# Control_Acceso.net
KiCad netlist of a schematic drawn in Altium Designer
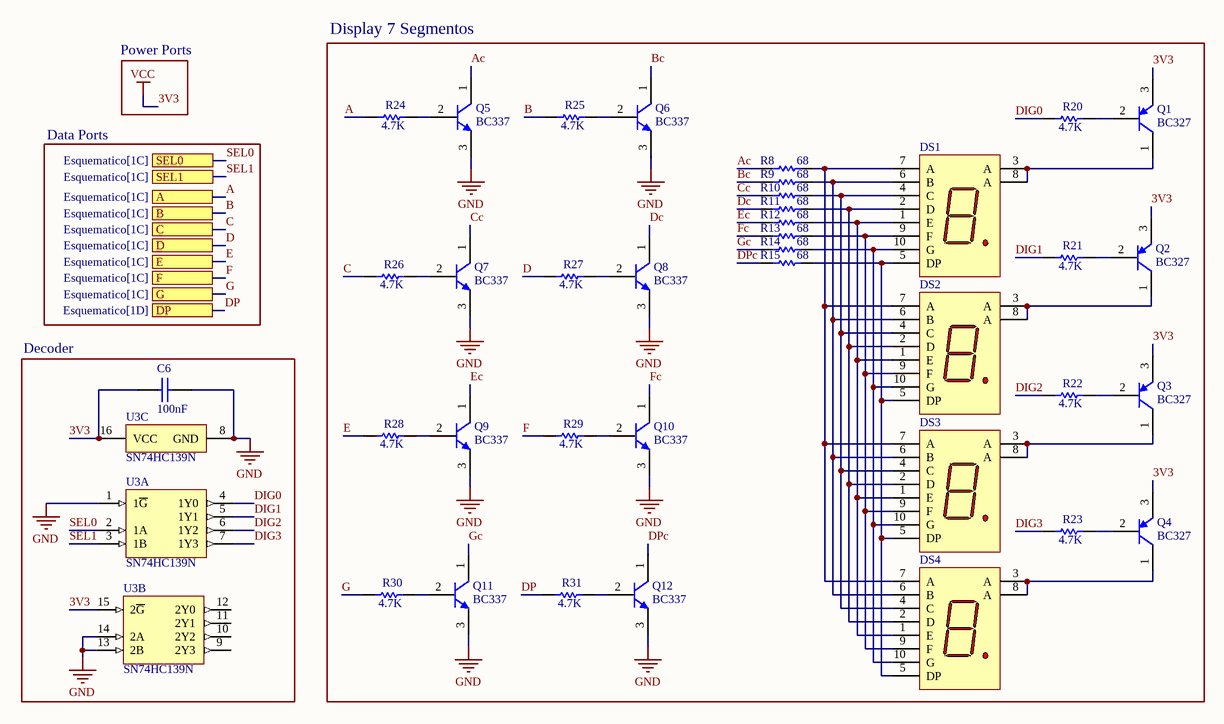
[diagram p0: Control_Acceso.SchDoc]

(export (version "E")
  (design (tool "Eeschema 10.0.6"))
  (components
    (comp (ref "C6")
      (value "100nF")
      (footprint "CAP200")
      (description "Multilayer Ceramic Capacitor")
      (libsource (lib "LIB PIO IX") (part "CAP"))
    )
    (comp (ref "DS1")
      (value "~")
      (footprint "WL-T7DS_L17.5W12.4H7")
      (description "7-Seg Display, Comm Anode, Super Red Rohs Compliant: Yes")
      (libsource (lib "Altium Content Vault") (part "7 Segments_Red_CA_type 1"))
    )
    (comp (ref "DS2")
      (value "~")
      (footprint "WL-T7DS_L17.5W12.4H7")
      (description "7-Seg Display, Comm Anode, Super Red Rohs Compliant: Yes")
      (libsource (lib "Altium Content Vault") (part "7 Segments_Red_CA_type 1"))
    )
    (comp (ref "DS3")
      (value "~")
      (footprint "WL-T7DS_L17.5W12.4H7")
      (description "7-Seg Display, Comm Anode, Super Red Rohs Compliant: Yes")
      (libsource (lib "Altium Content Vault") (part "7 Segments_Red_CA_type 1"))
    )
    (comp (ref "DS4")
      (value "~")
      (footprint "WL-T7DS_L17.5W12.4H7")
      (description "7-Seg Display, Comm Anode, Super Red Rohs Compliant: Yes")
      (libsource (lib "Altium Content Vault") (part "7 Segments_Red_CA_type 1"))
    )
    (comp (ref "Q1")
      (value "BC327")
      (footprint "ONSC-TO-92-3-29-11_AM_BL")
      (description "Amplifier Transistor, PNP Silicon, 3-Pin TO-92, Pb-Free, Ammo Box")
      (fields (field (name "MANUFACTURER") "On Semiconductor") (field (name "PARTNUMBER") "BC327-25ZL1G"))
      (libsource (lib "Altium Content Vault") (part "ONSC-PNP-C1B2E3-3"))
    )
    (comp (ref "Q2")
      (value "BC327")
      (footprint "ONSC-TO-92-3-29-11_AM_BL")
      (description "Amplifier Transistor, PNP Silicon, 3-Pin TO-92, Pb-Free, Ammo Box")
      (fields (field (name "MANUFACTURER") "On Semiconductor") (field (name "PARTNUMBER") "BC327-25ZL1G"))
      (libsource (lib "Altium Content Vault") (part "ONSC-PNP-C1B2E3-3"))
    )
    (comp (ref "Q3")
      (value "BC327")
      (footprint "ONSC-TO-92-3-29-11_AM_BL")
      (description "Amplifier Transistor, PNP Silicon, 3-Pin TO-92, Pb-Free, Ammo Box")
      (fields (field (name "MANUFACTURER") "On Semiconductor") (field (name "PARTNUMBER") "BC327-25ZL1G"))
      (libsource (lib "Altium Content Vault") (part "ONSC-PNP-C1B2E3-3"))
    )
    (comp (ref "Q4")
      (value "BC327")
      (footprint "ONSC-TO-92-3-29-11_AM_BL")
      (description "Amplifier Transistor, PNP Silicon, 3-Pin TO-92, Pb-Free, Ammo Box")
      (fields (field (name "MANUFACTURER") "On Semiconductor") (field (name "PARTNUMBER") "BC327-25ZL1G"))
      (libsource (lib "Altium Content Vault") (part "ONSC-PNP-C1B2E3-3"))
    )
    (comp (ref "Q5")
      (value "BC337")
      (footprint "ONSC-TO-92-3-29-11_AM_BL")
      (description "Amplifier Transistor, NPN Silicon, 3-Pin TO-92, Pb-Free, Ammo Box")
      (fields (field (name "PARTNUMBER") "BC337-40ZL1G") (field (name "MANUFACTURER") "On Semiconductor"))
      (libsource (lib "Altium Content Vault") (part "ONSC-NPN-C1B2E3-3"))
    )
    (comp (ref "Q6")
      (value "BC337")
      (footprint "ONSC-TO-92-3-29-11_AM_BL")
      (description "Amplifier Transistor, NPN Silicon, 3-Pin TO-92, Pb-Free, Ammo Box")
      (fields (field (name "PARTNUMBER") "BC337-40ZL1G") (field (name "MANUFACTURER") "On Semiconductor"))
      (libsource (lib "Altium Content Vault") (part "ONSC-NPN-C1B2E3-3"))
    )
    (comp (ref "Q7")
      (value "BC337")
      (footprint "ONSC-TO-92-3-29-11_AM_BL")
      (description "Amplifier Transistor, NPN Silicon, 3-Pin TO-92, Pb-Free, Ammo Box")
      (fields (field (name "PARTNUMBER") "BC337-40ZL1G") (field (name "MANUFACTURER") "On Semiconductor"))
      (libsource (lib "Altium Content Vault") (part "ONSC-NPN-C1B2E3-3"))
    )
    (comp (ref "Q8")
      (value "BC337")
      (footprint "ONSC-TO-92-3-29-11_AM_BL")
      (description "Amplifier Transistor, NPN Silicon, 3-Pin TO-92, Pb-Free, Ammo Box")
      (fields (field (name "PARTNUMBER") "BC337-40ZL1G") (field (name "MANUFACTURER") "On Semiconductor"))
      (libsource (lib "Altium Content Vault") (part "ONSC-NPN-C1B2E3-3"))
    )
    (comp (ref "Q9")
      (value "BC337")
      (footprint "ONSC-TO-92-3-29-11_AM_BL")
      (description "Amplifier Transistor, NPN Silicon, 3-Pin TO-92, Pb-Free, Ammo Box")
      (fields (field (name "PARTNUMBER") "BC337-40ZL1G") (field (name "MANUFACTURER") "On Semiconductor"))
      (libsource (lib "Altium Content Vault") (part "ONSC-NPN-C1B2E3-3"))
    )
    (comp (ref "Q10")
      (value "BC337")
      (footprint "ONSC-TO-92-3-29-11_AM_BL")
      (description "Amplifier Transistor, NPN Silicon, 3-Pin TO-92, Pb-Free, Ammo Box")
      (fields (field (name "PARTNUMBER") "BC337-40ZL1G") (field (name "MANUFACTURER") "On Semiconductor"))
      (libsource (lib "Altium Content Vault") (part "ONSC-NPN-C1B2E3-3"))
    )
    (comp (ref "Q11")
      (value "BC337")
      (footprint "ONSC-TO-92-3-29-11_AM_BL")
      (description "Amplifier Transistor, NPN Silicon, 3-Pin TO-92, Pb-Free, Ammo Box")
      (fields (field (name "PARTNUMBER") "BC337-40ZL1G") (field (name "MANUFACTURER") "On Semiconductor"))
      (libsource (lib "Altium Content Vault") (part "ONSC-NPN-C1B2E3-3"))
    )
    (comp (ref "Q12")
      (value "BC337")
      (footprint "ONSC-TO-92-3-29-11_AM_BL")
      (description "Amplifier Transistor, NPN Silicon, 3-Pin TO-92, Pb-Free, Ammo Box")
      (fields (field (name "PARTNUMBER") "BC337-40ZL1G") (field (name "MANUFACTURER") "On Semiconductor"))
      (libsource (lib "Altium Content Vault") (part "ONSC-NPN-C1B2E3-3"))
    )
    (comp (ref "R8")
      (value "68")
      (footprint "RES400")
      (description "Through Hole Resistor 1/8W Carbon Film")
      (libsource (lib "LIB PIO IX") (part "RES"))
    )
    (comp (ref "R9")
      (value "68")
      (footprint "RES400")
      (description "Through Hole Resistor 1/8W Carbon Film")
      (libsource (lib "LIB PIO IX") (part "RES"))
    )
    (comp (ref "R10")
      (value "68")
      (footprint "RES400")
      (description "Through Hole Resistor 1/8W Carbon Film")
      (libsource (lib "LIB PIO IX") (part "RES"))
    )
    (comp (ref "R11")
      (value "68")
      (footprint "RES400")
      (description "Through Hole Resistor 1/8W Carbon Film")
      (libsource (lib "LIB PIO IX") (part "RES"))
    )
    (comp (ref "R12")
      (value "68")
      (footprint "RES400")
      (description "Through Hole Resistor 1/8W Carbon Film")
      (libsource (lib "LIB PIO IX") (part "RES"))
    )
    (comp (ref "R13")
      (value "68")
      (footprint "RES400")
      (description "Through Hole Resistor 1/8W Carbon Film")
      (libsource (lib "LIB PIO IX") (part "RES"))
    )
    (comp (ref "R14")
      (value "68")
      (footprint "RES400")
      (description "Through Hole Resistor 1/8W Carbon Film")
      (libsource (lib "LIB PIO IX") (part "RES"))
    )
    (comp (ref "R15")
      (value "68")
      (footprint "RES400")
      (description "Through Hole Resistor 1/8W Carbon Film")
      (libsource (lib "LIB PIO IX") (part "RES"))
    )
    (comp (ref "R20")
      (value "4.7K")
      (footprint "RES400")
      (description "Through Hole Resistor 1/8W Carbon Film")
      (libsource (lib "LIB PIO IX") (part "RES"))
    )
    (comp (ref "R21")
      (value "4.7K")
      (footprint "RES400")
      (description "Through Hole Resistor 1/8W Carbon Film")
      (libsource (lib "LIB PIO IX") (part "RES"))
    )
    (comp (ref "R22")
      (value "4.7K")
      (footprint "RES400")
      (description "Through Hole Resistor 1/8W Carbon Film")
      (libsource (lib "LIB PIO IX") (part "RES"))
    )
    (comp (ref "R23")
      (value "4.7K")
      (footprint "RES400")
      (description "Through Hole Resistor 1/8W Carbon Film")
      (libsource (lib "LIB PIO IX") (part "RES"))
    )
    (comp (ref "R24")
      (value "4.7K")
      (footprint "RES400")
      (description "Through Hole Resistor 1/8W Carbon Film")
      (libsource (lib "LIB PIO IX") (part "RES"))
    )
    (comp (ref "R25")
      (value "4.7K")
      (footprint "RES400")
      (description "Through Hole Resistor 1/8W Carbon Film")
      (libsource (lib "LIB PIO IX") (part "RES"))
    )
    (comp (ref "R26")
      (value "4.7K")
      (footprint "RES400")
      (description "Through Hole Resistor 1/8W Carbon Film")
      (libsource (lib "LIB PIO IX") (part "RES"))
    )
    (comp (ref "R27")
      (value "4.7K")
      (footprint "RES400")
      (description "Through Hole Resistor 1/8W Carbon Film")
      (libsource (lib "LIB PIO IX") (part "RES"))
    )
    (comp (ref "R28")
      (value "4.7K")
      (footprint "RES400")
      (description "Through Hole Resistor 1/8W Carbon Film")
      (libsource (lib "LIB PIO IX") (part "RES"))
    )
    (comp (ref "R29")
      (value "4.7K")
      (footprint "RES400")
      (description "Through Hole Resistor 1/8W Carbon Film")
      (libsource (lib "LIB PIO IX") (part "RES"))
    )
    (comp (ref "R30")
      (value "4.7K")
      (footprint "RES400")
      (description "Through Hole Resistor 1/8W Carbon Film")
      (libsource (lib "LIB PIO IX") (part "RES"))
    )
    (comp (ref "R31")
      (value "4.7K")
      (footprint "RES400")
      (description "Through Hole Resistor 1/8W Carbon Film")
      (libsource (lib "LIB PIO IX") (part "RES"))
    )
    (comp (ref "U3")
      (value "SN74HC139N")
      (footprint "N0016A")
      (description "Dual 2-Line To 4-Line Decoders/Demultiplexers, N0016A, TUBE")
      (fields
        (field (name "GENERIC PART NUMBER") "SN74HC139")
        (field (name "MANUFACTURER") "Texas Instruments")
      )
      (libsource (lib "Altium Content Vault") (part "TI-CD_SNX4XXX139-16"))
    )
  )
  (nets
    (net (code "1") (name "/A") (class "Default")
      (node (ref "R24") (pin "1") (pinfunction "1_1") (pintype "passive"))
    )
    (net (code "2") (name "/Ac") (class "Default")
      (node (ref "Q5") (pin "1") (pinfunction "C_1") (pintype "passive"))
      (node (ref "R8") (pin "1") (pinfunction "1_1") (pintype "passive"))
    )
    (net (code "3") (name "/B") (class "Default")
      (node (ref "R25") (pin "1") (pinfunction "1_1") (pintype "passive"))
    )
    (net (code "4") (name "/Bc") (class "Default")
      (node (ref "Q6") (pin "1") (pinfunction "C_1") (pintype "passive"))
      (node (ref "R9") (pin "1") (pinfunction "1_1") (pintype "passive"))
    )
    (net (code "5") (name "/C") (class "Default")
      (node (ref "R26") (pin "1") (pinfunction "1_1") (pintype "passive"))
    )
    (net (code "6") (name "/Cc") (class "Default")
      (node (ref "Q7") (pin "1") (pinfunction "C_1") (pintype "passive"))
      (node (ref "R10") (pin "1") (pinfunction "1_1") (pintype "passive"))
    )
    (net (code "7") (name "/D") (class "Default")
      (node (ref "R27") (pin "1") (pinfunction "1_1") (pintype "passive"))
    )
    (net (code "8") (name "/DIG0") (class "Default")
      (node (ref "R20") (pin "1") (pinfunction "1_1") (pintype "passive"))
      (node (ref "U3") (pin "4") (pinfunction "1Y0_4") (pintype "output"))
    )
    (net (code "9") (name "/DIG1") (class "Default")
      (node (ref "R21") (pin "1") (pinfunction "1_1") (pintype "passive"))
      (node (ref "U3") (pin "5") (pinfunction "1Y1_5") (pintype "output"))
    )
    (net (code "10") (name "/DIG2") (class "Default")
      (node (ref "R22") (pin "1") (pinfunction "1_1") (pintype "passive"))
      (node (ref "U3") (pin "6") (pinfunction "1Y2_6") (pintype "output"))
    )
    (net (code "11") (name "/DIG3") (class "Default")
      (node (ref "R23") (pin "1") (pinfunction "1_1") (pintype "passive"))
      (node (ref "U3") (pin "7") (pinfunction "1Y3_7") (pintype "output"))
    )
    (net (code "12") (name "/DP") (class "Default")
      (node (ref "R31") (pin "1") (pinfunction "1_1") (pintype "passive"))
    )
    (net (code "13") (name "/DPc") (class "Default")
      (node (ref "Q12") (pin "1") (pinfunction "C_1") (pintype "passive"))
      (node (ref "R15") (pin "1") (pinfunction "1_1") (pintype "passive"))
    )
    (net (code "14") (name "/Dc") (class "Default")
      (node (ref "Q8") (pin "1") (pinfunction "C_1") (pintype "passive"))
      (node (ref "R11") (pin "1") (pinfunction "1_1") (pintype "passive"))
    )
    (net (code "15") (name "/E") (class "Default")
      (node (ref "R28") (pin "1") (pinfunction "1_1") (pintype "passive"))
    )
    (net (code "16") (name "/Ec") (class "Default")
      (node (ref "Q9") (pin "1") (pinfunction "C_1") (pintype "passive"))
      (node (ref "R12") (pin "1") (pinfunction "1_1") (pintype "passive"))
    )
    (net (code "17") (name "/F") (class "Default")
      (node (ref "R29") (pin "1") (pinfunction "1_1") (pintype "passive"))
    )
    (net (code "18") (name "/Fc") (class "Default")
      (node (ref "Q10") (pin "1") (pinfunction "C_1") (pintype "passive"))
      (node (ref "R13") (pin "1") (pinfunction "1_1") (pintype "passive"))
    )
    (net (code "19") (name "/G") (class "Default")
      (node (ref "R30") (pin "1") (pinfunction "1_1") (pintype "passive"))
    )
    (net (code "20") (name "/Gc") (class "Default")
      (node (ref "Q11") (pin "1") (pinfunction "C_1") (pintype "passive"))
      (node (ref "R14") (pin "1") (pinfunction "1_1") (pintype "passive"))
    )
    (net (code "21") (name "/SEL0") (class "Default")
      (node (ref "U3") (pin "2") (pinfunction "1A_2") (pintype "input"))
    )
    (net (code "22") (name "/SEL1") (class "Default")
      (node (ref "U3") (pin "3") (pinfunction "1B_3") (pintype "input"))
    )
    (net (code "23") (name "GND") (class "Default")
      (node (ref "C6") (pin "2") (pinfunction "2_2") (pintype "passive"))
      (node (ref "Q10") (pin "3") (pinfunction "E_3") (pintype "passive"))
      (node (ref "Q11") (pin "3") (pinfunction "E_3") (pintype "passive"))
      (node (ref "Q12") (pin "3") (pinfunction "E_3") (pintype "passive"))
      (node (ref "Q5") (pin "3") (pinfunction "E_3") (pintype "passive"))
      (node (ref "Q6") (pin "3") (pinfunction "E_3") (pintype "passive"))
      (node (ref "Q7") (pin "3") (pinfunction "E_3") (pintype "passive"))
      (node (ref "Q8") (pin "3") (pinfunction "E_3") (pintype "passive"))
      (node (ref "Q9") (pin "3") (pinfunction "E_3") (pintype "passive"))
      (node (ref "U3") (pin "1") (pinfunction "1~{G}_1") (pintype "input"))
      (node (ref "U3") (pin "13") (pinfunction "2B_13") (pintype "input"))
      (node (ref "U3") (pin "14") (pinfunction "2A_14") (pintype "input"))
      (node (ref "U3") (pin "8") (pinfunction "GND_8") (pintype "power_in"))
    )
    (net (code "24") (name "Net-(DS1-A-Pad7)") (class "Default")
      (node (ref "DS1") (pin "7") (pinfunction "A_7") (pintype "passive"))
      (node (ref "DS2") (pin "7") (pinfunction "A_7") (pintype "passive"))
      (node (ref "DS3") (pin "7") (pinfunction "A_7") (pintype "passive"))
      (node (ref "DS4") (pin "7") (pinfunction "A_7") (pintype "passive"))
      (node (ref "R8") (pin "2") (pinfunction "2_2") (pintype "passive"))
    )
    (net (code "25") (name "Net-(DS1-B)") (class "Default")
      (node (ref "DS1") (pin "6") (pinfunction "B_6") (pintype "passive"))
      (node (ref "DS2") (pin "6") (pinfunction "B_6") (pintype "passive"))
      (node (ref "DS3") (pin "6") (pinfunction "B_6") (pintype "passive"))
      (node (ref "DS4") (pin "6") (pinfunction "B_6") (pintype "passive"))
      (node (ref "R9") (pin "2") (pinfunction "2_2") (pintype "passive"))
    )
    (net (code "26") (name "Net-(DS1-C)") (class "Default")
      (node (ref "DS1") (pin "4") (pinfunction "C_4") (pintype "passive"))
      (node (ref "DS2") (pin "4") (pinfunction "C_4") (pintype "passive"))
      (node (ref "DS3") (pin "4") (pinfunction "C_4") (pintype "passive"))
      (node (ref "DS4") (pin "4") (pinfunction "C_4") (pintype "passive"))
      (node (ref "R10") (pin "2") (pinfunction "2_2") (pintype "passive"))
    )
    (net (code "27") (name "Net-(DS1-D)") (class "Default")
      (node (ref "DS1") (pin "2") (pinfunction "D_2") (pintype "passive"))
      (node (ref "DS2") (pin "2") (pinfunction "D_2") (pintype "passive"))
      (node (ref "DS3") (pin "2") (pinfunction "D_2") (pintype "passive"))
      (node (ref "DS4") (pin "2") (pinfunction "D_2") (pintype "passive"))
      (node (ref "R11") (pin "2") (pinfunction "2_2") (pintype "passive"))
    )
    (net (code "28") (name "Net-(DS1-DP)") (class "Default")
      (node (ref "DS1") (pin "5") (pinfunction "DP_5") (pintype "passive"))
      (node (ref "DS2") (pin "5") (pinfunction "DP_5") (pintype "passive"))
      (node (ref "DS3") (pin "5") (pinfunction "DP_5") (pintype "passive"))
      (node (ref "DS4") (pin "5") (pinfunction "DP_5") (pintype "passive"))
      (node (ref "R15") (pin "2") (pinfunction "2_2") (pintype "passive"))
    )
    (net (code "29") (name "Net-(DS1-E)") (class "Default")
      (node (ref "DS1") (pin "1") (pinfunction "E_1") (pintype "passive"))
      (node (ref "DS2") (pin "1") (pinfunction "E_1") (pintype "passive"))
      (node (ref "DS3") (pin "1") (pinfunction "E_1") (pintype "passive"))
      (node (ref "DS4") (pin "1") (pinfunction "E_1") (pintype "passive"))
      (node (ref "R12") (pin "2") (pinfunction "2_2") (pintype "passive"))
    )
    (net (code "30") (name "Net-(DS1-F)") (class "Default")
      (node (ref "DS1") (pin "9") (pinfunction "F_9") (pintype "passive"))
      (node (ref "DS2") (pin "9") (pinfunction "F_9") (pintype "passive"))
      (node (ref "DS3") (pin "9") (pinfunction "F_9") (pintype "passive"))
      (node (ref "DS4") (pin "9") (pinfunction "F_9") (pintype "passive"))
      (node (ref "R13") (pin "2") (pinfunction "2_2") (pintype "passive"))
    )
    (net (code "31") (name "Net-(DS1-G)") (class "Default")
      (node (ref "DS1") (pin "10") (pinfunction "G_10") (pintype "passive"))
      (node (ref "DS2") (pin "10") (pinfunction "G_10") (pintype "passive"))
      (node (ref "DS3") (pin "10") (pinfunction "G_10") (pintype "passive"))
      (node (ref "DS4") (pin "10") (pinfunction "G_10") (pintype "passive"))
      (node (ref "R14") (pin "2") (pinfunction "2_2") (pintype "passive"))
    )
    (net (code "32") (name "Net-(Q1-B)") (class "Default")
      (node (ref "Q1") (pin "2") (pinfunction "B_2") (pintype "passive"))
      (node (ref "R20") (pin "2") (pinfunction "2_2") (pintype "passive"))
    )
    (net (code "33") (name "Net-(Q1-C)") (class "Default")
      (node (ref "DS1") (pin "3") (pinfunction "A_3") (pintype "passive"))
      (node (ref "DS1") (pin "8") (pinfunction "A_8") (pintype "passive"))
      (node (ref "Q1") (pin "1") (pinfunction "C_1") (pintype "passive"))
    )
    (net (code "34") (name "Net-(Q2-B)") (class "Default")
      (node (ref "Q2") (pin "2") (pinfunction "B_2") (pintype "passive"))
      (node (ref "R21") (pin "2") (pinfunction "2_2") (pintype "passive"))
    )
    (net (code "35") (name "Net-(Q2-C)") (class "Default")
      (node (ref "DS2") (pin "3") (pinfunction "A_3") (pintype "passive"))
      (node (ref "DS2") (pin "8") (pinfunction "A_8") (pintype "passive"))
      (node (ref "Q2") (pin "1") (pinfunction "C_1") (pintype "passive"))
    )
    (net (code "36") (name "Net-(Q3-B)") (class "Default")
      (node (ref "Q3") (pin "2") (pinfunction "B_2") (pintype "passive"))
      (node (ref "R22") (pin "2") (pinfunction "2_2") (pintype "passive"))
    )
    (net (code "37") (name "Net-(Q3-C)") (class "Default")
      (node (ref "DS3") (pin "3") (pinfunction "A_3") (pintype "passive"))
      (node (ref "DS3") (pin "8") (pinfunction "A_8") (pintype "passive"))
      (node (ref "Q3") (pin "1") (pinfunction "C_1") (pintype "passive"))
    )
    (net (code "38") (name "Net-(Q4-B)") (class "Default")
      (node (ref "Q4") (pin "2") (pinfunction "B_2") (pintype "passive"))
      (node (ref "R23") (pin "2") (pinfunction "2_2") (pintype "passive"))
    )
    (net (code "39") (name "Net-(Q4-C)") (class "Default")
      (node (ref "DS4") (pin "3") (pinfunction "A_3") (pintype "passive"))
      (node (ref "DS4") (pin "8") (pinfunction "A_8") (pintype "passive"))
      (node (ref "Q4") (pin "1") (pinfunction "C_1") (pintype "passive"))
    )
    (net (code "40") (name "Net-(Q5-B)") (class "Default")
      (node (ref "Q5") (pin "2") (pinfunction "B_2") (pintype "passive"))
      (node (ref "R24") (pin "2") (pinfunction "2_2") (pintype "passive"))
    )
    (net (code "41") (name "Net-(Q6-B)") (class "Default")
      (node (ref "Q6") (pin "2") (pinfunction "B_2") (pintype "passive"))
      (node (ref "R25") (pin "2") (pinfunction "2_2") (pintype "passive"))
    )
    (net (code "42") (name "Net-(Q7-B)") (class "Default")
      (node (ref "Q7") (pin "2") (pinfunction "B_2") (pintype "passive"))
      (node (ref "R26") (pin "2") (pinfunction "2_2") (pintype "passive"))
    )
    (net (code "43") (name "Net-(Q8-B)") (class "Default")
      (node (ref "Q8") (pin "2") (pinfunction "B_2") (pintype "passive"))
      (node (ref "R27") (pin "2") (pinfunction "2_2") (pintype "passive"))
    )
    (net (code "44") (name "Net-(Q9-B)") (class "Default")
      (node (ref "Q9") (pin "2") (pinfunction "B_2") (pintype "passive"))
      (node (ref "R28") (pin "2") (pinfunction "2_2") (pintype "passive"))
    )
    (net (code "45") (name "Net-(Q10-B)") (class "Default")
      (node (ref "Q10") (pin "2") (pinfunction "B_2") (pintype "passive"))
      (node (ref "R29") (pin "2") (pinfunction "2_2") (pintype "passive"))
    )
    (net (code "46") (name "Net-(Q11-B)") (class "Default")
      (node (ref "Q11") (pin "2") (pinfunction "B_2") (pintype "passive"))
      (node (ref "R30") (pin "2") (pinfunction "2_2") (pintype "passive"))
    )
    (net (code "47") (name "Net-(Q12-B)") (class "Default")
      (node (ref "Q12") (pin "2") (pinfunction "B_2") (pintype "passive"))
      (node (ref "R31") (pin "2") (pinfunction "2_2") (pintype "passive"))
    )
    (net (code "48") (name "VCC") (class "Default")
      (node (ref "C6") (pin "1") (pinfunction "1_1") (pintype "passive"))
      (node (ref "Q1") (pin "3") (pinfunction "E_3") (pintype "passive"))
      (node (ref "Q2") (pin "3") (pinfunction "E_3") (pintype "passive"))
      (node (ref "Q3") (pin "3") (pinfunction "E_3") (pintype "passive"))
      (node (ref "Q4") (pin "3") (pinfunction "E_3") (pintype "passive"))
      (node (ref "U3") (pin "15") (pinfunction "2~{G}_15") (pintype "input"))
      (node (ref "U3") (pin "16") (pinfunction "VCC_16") (pintype "power_in"))
    )
    (net (code "49") (name "unconnected-(U3B-2Y0-Pad12)") (class "Default")
      (node (ref "U3") (pin "12") (pinfunction "2Y0_12") (pintype "output"))
    )
    (net (code "50") (name "unconnected-(U3B-2Y1-Pad11)") (class "Default")
      (node (ref "U3") (pin "11") (pinfunction "2Y1_11") (pintype "output"))
    )
    (net (code "51") (name "unconnected-(U3B-2Y2-Pad10)") (class "Default")
      (node (ref "U3") (pin "10") (pinfunction "2Y2_10") (pintype "output"))
    )
    (net (code "52") (name "unconnected-(U3B-2Y3-Pad9)") (class "Default")
      (node (ref "U3") (pin "9") (pinfunction "2Y3_9") (pintype "output"))
    )
  )
)
